# Roomba2.net
KiCad netlist of a schematic drawn in EAGLE
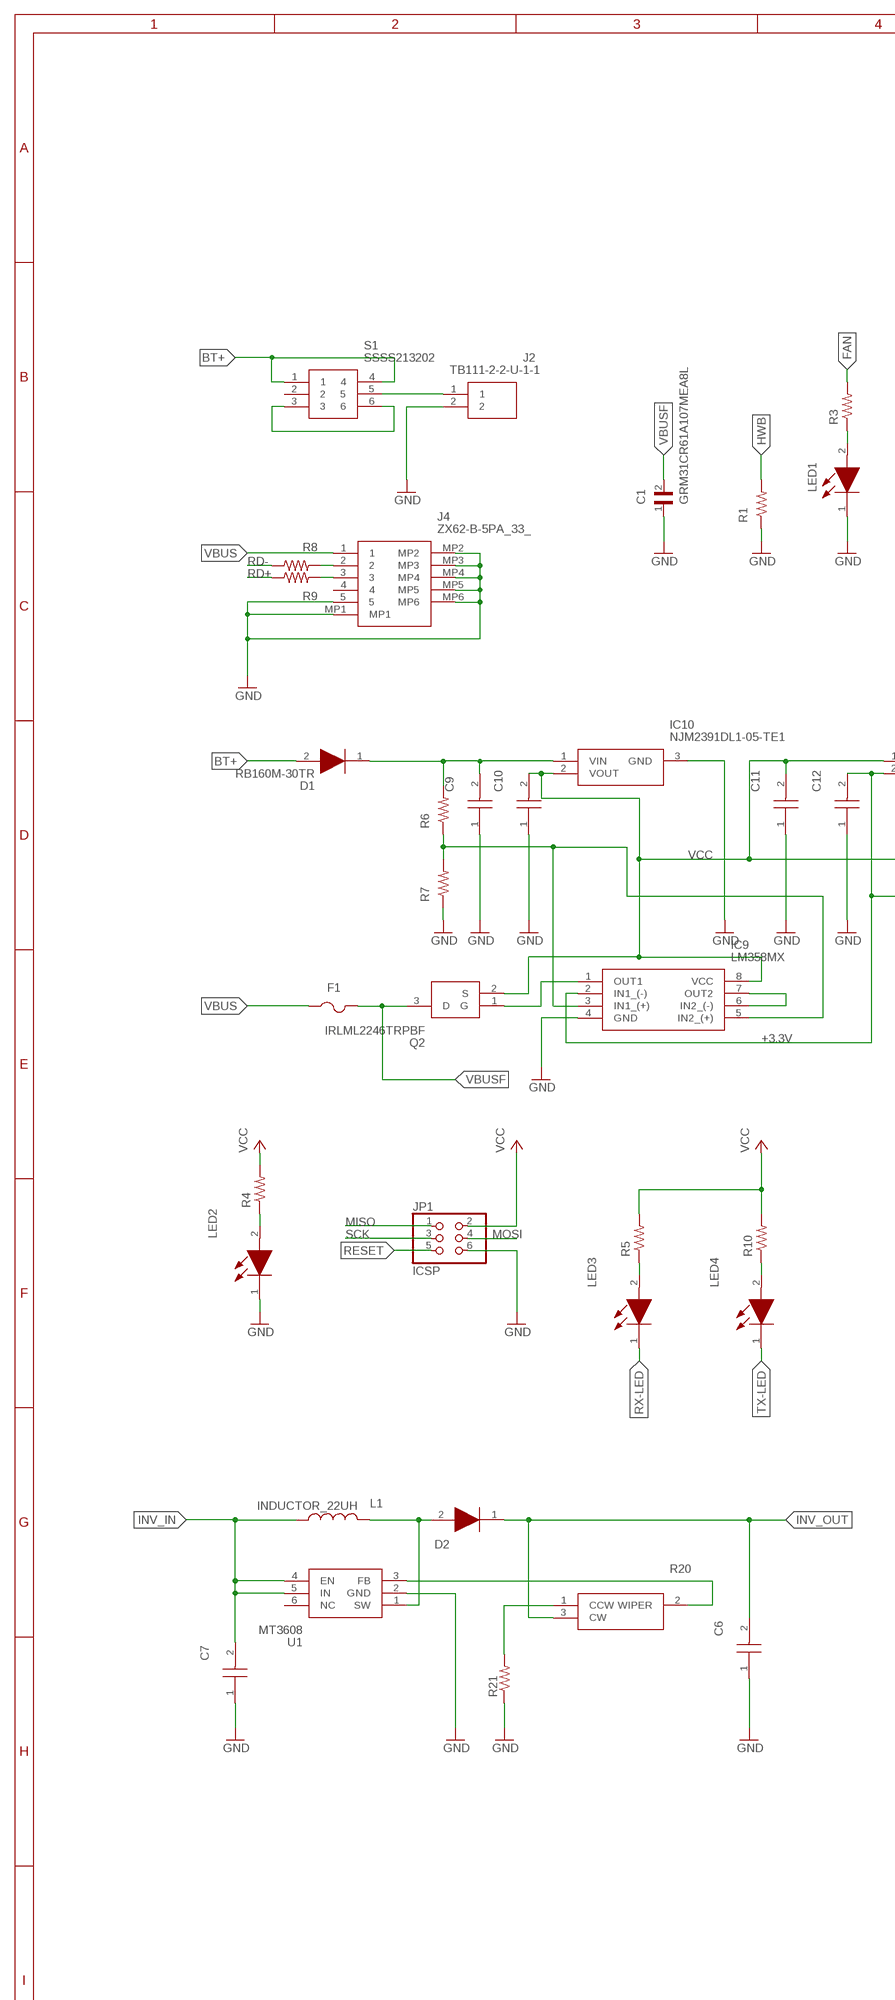
[diagram p0: schematic, sheet 1, part 1 of 2]
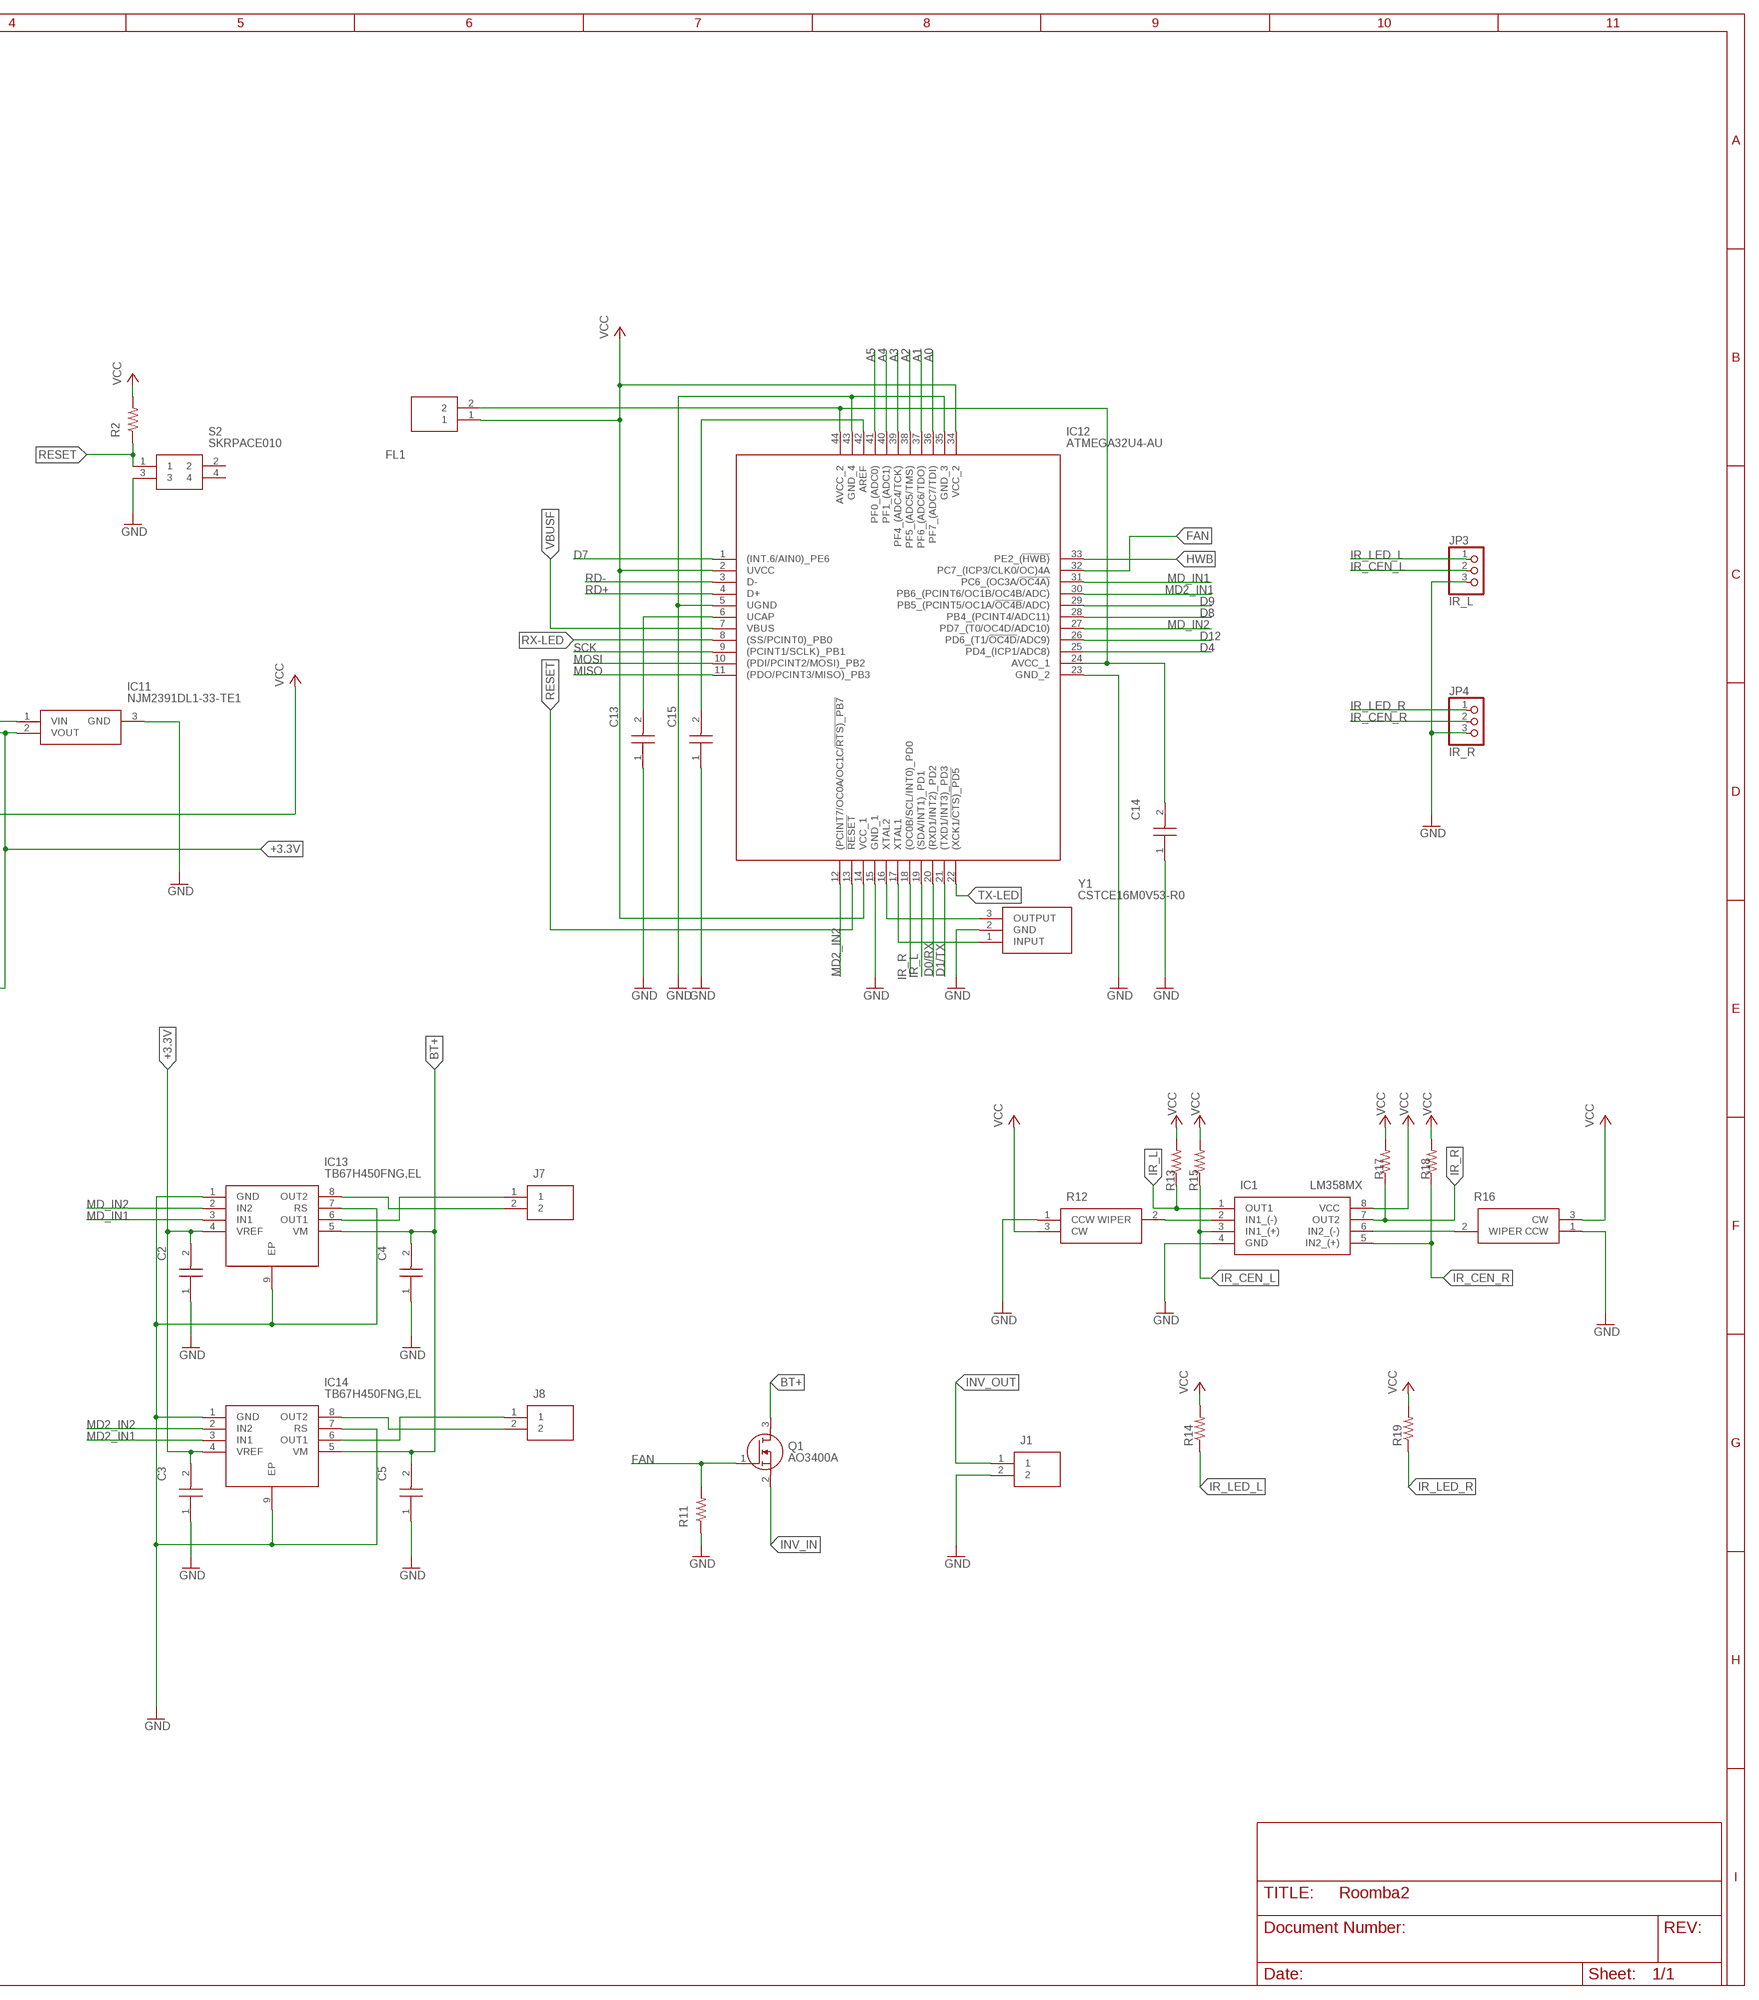
[diagram p1: schematic, sheet 1, part 2 of 2]

(export (version "E")
  (design (tool "Eeschema 10.0.6"))
  (components
    (comp (ref "C1")
      (value "GRM31CR61A107MEA8L")
      (footprint "eagle-import:CAPC3216X190N")
      (fields (field (name "MF") "Murata"))
      (libsource (lib "eagle-import") (part "GRM31CR61A107MEA8L"))
    )
    (comp (ref "C2")
      (value "GRM188F11H104ZA01B")
      (footprint "eagle-import:CAPC1608X90N")
      (libsource (lib "eagle-import") (part "GRM188F11H104ZA01B"))
    )
    (comp (ref "C3")
      (value "GRM188F11H104ZA01B")
      (footprint "eagle-import:CAPC1608X90N")
      (libsource (lib "eagle-import") (part "GRM188F11H104ZA01B"))
    )
    (comp (ref "C4")
      (value "GRM188F11H104ZA01B")
      (footprint "eagle-import:CAPC1608X90N")
      (libsource (lib "eagle-import") (part "GRM188F11H104ZA01B"))
    )
    (comp (ref "C5")
      (value "GRM188F11H104ZA01B")
      (footprint "eagle-import:CAPC1608X90N")
      (libsource (lib "eagle-import") (part "GRM188F11H104ZA01B"))
    )
    (comp (ref "C6")
      (value "GRM31CB31E226KE15L")
      (footprint "eagle-import:CAPC3216X180N")
      (libsource (lib "eagle-import") (part "GRM31CB31E226KE15L"))
    )
    (comp (ref "C7")
      (value "GRM31CB31E226KE15L")
      (footprint "eagle-import:CAPC3216X180N")
      (libsource (lib "eagle-import") (part "GRM31CB31E226KE15L"))
    )
    (comp (ref "C9")
      (value "GRM188F11H104ZA01B")
      (footprint "eagle-import:CAPC1608X90N")
      (libsource (lib "eagle-import") (part "GRM188F11H104ZA01B"))
    )
    (comp (ref "C10")
      (value "GRM31CB31A476KE15L")
      (footprint "eagle-import:CAPC3216X180N")
      (libsource (lib "eagle-import") (part "GRM31CB31A476KE15L"))
    )
    (comp (ref "C11")
      (value "GRM188F11H104ZA01B")
      (footprint "eagle-import:CAPC1608X90N")
      (libsource (lib "eagle-import") (part "GRM188F11H104ZA01B"))
    )
    (comp (ref "C12")
      (value "GRM31CB31A476KE15L")
      (footprint "eagle-import:CAPC3216X180N")
      (libsource (lib "eagle-import") (part "GRM31CB31A476KE15L"))
    )
    (comp (ref "C13")
      (value "GRM188R71E105KA12D")
      (footprint "eagle-import:CAPC1608X90N")
      (fields (field (name "MOUSER_PART_NUMBER") "81-GRM188R71E105KA2D"))
      (libsource (lib "eagle-import") (part "GRM188R71E105KA12D"))
    )
    (comp (ref "C14")
      (value "GRM188R71E105KA12D")
      (footprint "eagle-import:CAPC1608X90N")
      (fields (field (name "MOUSER_PART_NUMBER") "81-GRM188R71E105KA2D"))
      (libsource (lib "eagle-import") (part "GRM188R71E105KA12D"))
    )
    (comp (ref "C15")
      (value "GRM188F11H104ZA01B")
      (footprint "eagle-import:CAPC1608X90N")
      (libsource (lib "eagle-import") (part "GRM188F11H104ZA01B"))
    )
    (comp (ref "D1")
      (value "RB160M-30TR")
      (footprint "eagle-import:SODFL3516X90N")
      (fields (field (name "MOUSER_PART_NUMBER") "755-RB160M-30TR"))
      (libsource (lib "eagle-import") (part "RB160M-30TR"))
    )
    (comp (ref "D2")
      (value "SS2040FL")
      (footprint "eagle-import:SODFL3618X108N")
      (libsource (lib "eagle-import") (part "SS2040FL"))
    )
    (comp (ref "F1")
      (value "MF-MSMF010-2")
      (footprint "eagle-import:FUSC4632X110N")
      (fields (field (name "MOUSER_PART_NUMBER") "652-MF-MSMF010-2"))
      (libsource (lib "eagle-import") (part "MF-MSMF010-2"))
    )
    (comp (ref "FL1")
      (value "BLM18PG600SN1D")
      (footprint "eagle-import:BLM18AG102BH1D")
      (fields (field (name "MOUSER_PART_NUMBER") "81-BLM11P600S"))
      (libsource (lib "eagle-import") (part "BLM18PG600SN1D"))
    )
    (comp (ref "IC1")
      (value "LM358MX")
      (footprint "eagle-import:SOIC127P600X175-8N")
      (fields (field (name "MOUSER_PART_NUMBER") "512-LM358MX"))
      (libsource (lib "eagle-import") (part "LM358MX"))
    )
    (comp (ref "IC9")
      (value "LM358MX")
      (footprint "eagle-import:SOIC127P600X175-8N")
      (fields (field (name "MOUSER_PART_NUMBER") "512-LM358MX"))
      (libsource (lib "eagle-import") (part "LM358MX"))
    )
    (comp (ref "IC10")
      (value "NJM2391DL1-05-TE1")
      (footprint "eagle-import:TO-252-3-L1_1")
      (fields (field (name "MOUSER_PART_NUMBER") "513-NJM2391DL105-TE1"))
      (libsource (lib "eagle-import") (part "NJM2391DL1-05-TE1"))
    )
    (comp (ref "IC11")
      (value "NJM2391DL1-33-TE1")
      (footprint "eagle-import:TO-252-3-L1")
      (fields (field (name "MOUSER_PART_NUMBER") "513-NJM2391DL133-TE1"))
      (libsource (lib "eagle-import") (part "NJM2391DL1-33-TE1"))
    )
    (comp (ref "IC12")
      (value "ATMEGA32U4-AU")
      (footprint "eagle-import:QFP80P1200X1200X120-44N")
      (fields (field (name "MOUSER_PART_NUMBER") "556-ATMEGA32U4-AU"))
      (libsource (lib "eagle-import") (part "ATMEGA32U4-AU"))
    )
    (comp (ref "IC13")
      (value "TB67H450FNG,EL")
      (footprint "eagle-import:SOIC127P600X175-9N")
      (fields (field (name "MOUSER_PART_NUMBER") "757-TB67H450FNGEL"))
      (libsource (lib "eagle-import") (part "TB67H450FNG,EL"))
    )
    (comp (ref "IC14")
      (value "TB67H450FNG,EL")
      (footprint "eagle-import:SOIC127P600X175-9N")
      (fields (field (name "MOUSER_PART_NUMBER") "757-TB67H450FNGEL"))
      (libsource (lib "eagle-import") (part "TB67H450FNG,EL"))
    )
    (comp (ref "J1")
      (value "TB111-2-2-U-1-1")
      (footprint "eagle-import:TB11122U11")
      (libsource (lib "eagle-import") (part "TB111-2-2-U-1-1"))
    )
    (comp (ref "J2")
      (value "TB111-2-2-U-1-1")
      (footprint "eagle-import:TB11122U11")
      (libsource (lib "eagle-import") (part "TB111-2-2-U-1-1"))
    )
    (comp (ref "J4")
      (value "ZX62-B-5PA_33_")
      (footprint "eagle-import:ZX62B5PA33")
      (fields
        (field (name "MANUFACTURER_PART_NUMBER") "ZX62-B-5PA(33)")
        (field (name "MOUSER_PART_NUMBER") "798-ZX62-B-5PA33")
      )
      (libsource (lib "eagle-import") (part "ZX62-B-5PA_33_"))
    )
    (comp (ref "J7")
      (value "TB111-2-2-U-1-1")
      (footprint "eagle-import:TB11122U11")
      (libsource (lib "eagle-import") (part "TB111-2-2-U-1-1"))
    )
    (comp (ref "J8")
      (value "TB111-2-2-U-1-1")
      (footprint "eagle-import:TB11122U11")
      (libsource (lib "eagle-import") (part "TB111-2-2-U-1-1"))
    )
    (comp (ref "JP1")
      (value "ICSP")
      (footprint "eagle-import:2X03")
      (libsource (lib "eagle-import") (part "PINHD-2X3"))
    )
    (comp (ref "JP3")
      (value "IR_L")
      (footprint "eagle-import:1X03")
      (libsource (lib "eagle-import") (part "PINHD-1X3"))
    )
    (comp (ref "JP4")
      (value "IR_R")
      (footprint "eagle-import:1X03")
      (libsource (lib "eagle-import") (part "PINHD-1X3"))
    )
    (comp (ref "L1")
      (value "INDUCTOR_22UH")
      (footprint "eagle-import:INDUCTOR_22UH")
      (libsource (lib "eagle-import") (part "INDUCTOR_22UH"))
    )
    (comp (ref "LED1")
      (value "SML-E12Y8WT86")
      (footprint "eagle-import:SMLE12Y8WT86")
      (fields (field (name "MOUSER_PART_NUMBER") "755-SML-E12Y8WT86"))
      (libsource (lib "eagle-import") (part "SML-E12Y8WT86"))
    )
    (comp (ref "LED2")
      (value "SML-E12P8WT86")
      (footprint "eagle-import:LEDC1608X36N")
      (fields (field (name "MOUSER_PART_NUMBER") "755-SML-E12P8WT86"))
      (libsource (lib "eagle-import") (part "SML-E12P8WT86"))
    )
    (comp (ref "LED3")
      (value "SML-E12Y8WT86")
      (footprint "eagle-import:SMLE12Y8WT86")
      (fields (field (name "MOUSER_PART_NUMBER") "755-SML-E12Y8WT86"))
      (libsource (lib "eagle-import") (part "SML-E12Y8WT86"))
    )
    (comp (ref "LED4")
      (value "SML-E12Y8WT86")
      (footprint "eagle-import:SMLE12Y8WT86")
      (fields (field (name "MOUSER_PART_NUMBER") "755-SML-E12Y8WT86"))
      (libsource (lib "eagle-import") (part "SML-E12Y8WT86"))
    )
    (comp (ref "Q1")
      (value "AO3400A")
      (footprint "eagle-import:SOT95P280X125-3N")
      (libsource (lib "eagle-import") (part "AO3400A"))
    )
    (comp (ref "Q2")
      (value "IRLML2246TRPBF")
      (footprint "eagle-import:SOT95P237X112-3N")
      (fields (field (name "MOUSER_PART_NUMBER") "942-IRLML2246TRPBF"))
      (libsource (lib "eagle-import") (part "IRLML2246TRPBF"))
    )
    (comp (ref "R1")
      (value "CRCW120610K0FKEA")
      (footprint "eagle-import:RESC3216X60N")
      (fields (field (name "MOUSER_PART_NUMBER") "71-CRCW1206-10K-E3"))
      (libsource (lib "eagle-import") (part "CRCW120610K0FKEA"))
    )
    (comp (ref "R2")
      (value "CRCW120610K0FKEA")
      (footprint "eagle-import:RESC3216X60N")
      (fields (field (name "MOUSER_PART_NUMBER") "71-CRCW1206-10K-E3"))
      (libsource (lib "eagle-import") (part "CRCW120610K0FKEA"))
    )
    (comp (ref "R3")
      (value "CRCW12061K00FKEA")
      (footprint "eagle-import:RESC3216X60N")
      (fields (field (name "MOUSER_PART_NUMBER") "71-CRCW1206-1.0K-E3"))
      (libsource (lib "eagle-import") (part "CRCW12061K00FKEA"))
    )
    (comp (ref "R4")
      (value "CRCW12061K00FKEA")
      (footprint "eagle-import:RESC3216X60N")
      (fields (field (name "MOUSER_PART_NUMBER") "71-CRCW1206-1.0K-E3"))
      (libsource (lib "eagle-import") (part "CRCW12061K00FKEA"))
    )
    (comp (ref "R5")
      (value "CRCW12061K00FKEA")
      (footprint "eagle-import:RESC3216X60N")
      (fields (field (name "MOUSER_PART_NUMBER") "71-CRCW1206-1.0K-E3"))
      (libsource (lib "eagle-import") (part "CRCW12061K00FKEA"))
    )
    (comp (ref "R6")
      (value "CRCW120610K0FKEA")
      (footprint "eagle-import:RESC3216X60N")
      (fields (field (name "MOUSER_PART_NUMBER") "71-CRCW1206-10K-E3"))
      (libsource (lib "eagle-import") (part "CRCW120610K0FKEA"))
    )
    (comp (ref "R7")
      (value "CRCW120610K0FKEA")
      (footprint "eagle-import:RESC3216X60N")
      (fields (field (name "MOUSER_PART_NUMBER") "71-CRCW1206-10K-E3"))
      (libsource (lib "eagle-import") (part "CRCW120610K0FKEA"))
    )
    (comp (ref "R8")
      (value "CRCW120622R0FKEA")
      (footprint "eagle-import:RESC3216X60N")
      (fields (field (name "MOUSER_PART_NUMBER") "71-CRCW1206-22-E3"))
      (libsource (lib "eagle-import") (part "CRCW120622R0FKEA"))
    )
    (comp (ref "R9")
      (value "CRCW120622R0FKEA")
      (footprint "eagle-import:RESC3216X60N")
      (fields (field (name "MOUSER_PART_NUMBER") "71-CRCW1206-22-E3"))
      (libsource (lib "eagle-import") (part "CRCW120622R0FKEA"))
    )
    (comp (ref "R10")
      (value "CRCW12061K00FKEA")
      (footprint "eagle-import:RESC3216X60N")
      (fields (field (name "MOUSER_PART_NUMBER") "71-CRCW1206-1.0K-E3"))
      (libsource (lib "eagle-import") (part "CRCW12061K00FKEA"))
    )
    (comp (ref "R11")
      (value "CRCW120610K0FKEA")
      (footprint "eagle-import:RESC3216X60N")
      (fields (field (name "MOUSER_PART_NUMBER") "71-CRCW1206-10K-E3"))
      (libsource (lib "eagle-import") (part "CRCW120610K0FKEA"))
    )
    (comp (ref "R12")
      (value "3362P-1-103")
      (footprint "eagle-import:3362P_1")
      (fields (field (name "MOUSER_PART_NUMBER") "652-3362P-1-103"))
      (libsource (lib "eagle-import") (part "3362P-1-103"))
    )
    (comp (ref "R13")
      (value "CRCW120610K0FKEA")
      (footprint "eagle-import:RESC3216X60N")
      (fields (field (name "MOUSER_PART_NUMBER") "71-CRCW1206-10K-E3"))
      (libsource (lib "eagle-import") (part "CRCW120610K0FKEA"))
    )
    (comp (ref "R14")
      (value "CRCW1206100RFKEB")
      (footprint "eagle-import:RESC3216X60N")
      (fields (field (name "MOUSER_PART_NUMBER") "71-CRCW1206100RFKEB"))
      (libsource (lib "eagle-import") (part "CRCW1206100RFKEB"))
    )
    (comp (ref "R15")
      (value "CRCW120610K0FKEA")
      (footprint "eagle-import:RESC3216X60N")
      (fields (field (name "MOUSER_PART_NUMBER") "71-CRCW1206-10K-E3"))
      (libsource (lib "eagle-import") (part "CRCW120610K0FKEA"))
    )
    (comp (ref "R16")
      (value "3362P-1-103")
      (footprint "eagle-import:3362P_1")
      (fields (field (name "MOUSER_PART_NUMBER") "652-3362P-1-103"))
      (libsource (lib "eagle-import") (part "3362P-1-103"))
    )
    (comp (ref "R17")
      (value "CRCW120610K0FKEA")
      (footprint "eagle-import:RESC3216X60N")
      (fields (field (name "MOUSER_PART_NUMBER") "71-CRCW1206-10K-E3"))
      (libsource (lib "eagle-import") (part "CRCW120610K0FKEA"))
    )
    (comp (ref "R18")
      (value "CRCW120610K0FKEA")
      (footprint "eagle-import:RESC3216X60N")
      (fields (field (name "MOUSER_PART_NUMBER") "71-CRCW1206-10K-E3"))
      (libsource (lib "eagle-import") (part "CRCW120610K0FKEA"))
    )
    (comp (ref "R19")
      (value "CRCW1206100RFKEB")
      (footprint "eagle-import:RESC3216X60N")
      (fields (field (name "MOUSER_PART_NUMBER") "71-CRCW1206100RFKEB"))
      (libsource (lib "eagle-import") (part "CRCW1206100RFKEB"))
    )
    (comp (ref "R20")
      (value "3362P-1-104LF")
      (footprint "eagle-import:3362P_1")
      (fields (field (name "MOUSER_PART_NUMBER") "652-3362P-1-104LF"))
      (libsource (lib "eagle-import") (part "3362P-1-104LF"))
    )
    (comp (ref "R21")
      (value "CRCW12062K20FKEA")
      (footprint "eagle-import:RESC3216X60N")
      (fields (field (name "MOUSER_PART_NUMBER") "71-CRCW1206-2.2K-E3"))
      (libsource (lib "eagle-import") (part "CRCW12062K20FKEA"))
    )
    (comp (ref "S1")
      (value "SSSS213202")
      (footprint "eagle-import:SSSS213202")
      (fields (field (name "MOUSER_PART_NUMBER") "688-SSSS213202"))
      (libsource (lib "eagle-import") (part "SSSS213202"))
    )
    (comp (ref "S2")
      (value "SKRPACE010")
      (footprint "eagle-import:SMT(4.2X3.2)")
      (fields (field (name "MOUSER_PART_NUMBER") "688-SKRPACE010"))
      (libsource (lib "eagle-import") (part "SKRPACE010"))
    )
    (comp (ref "U1")
      (value "MT3608")
      (footprint "eagle-import:SOT95P280X145-6N")
      (libsource (lib "eagle-import") (part "MT3608"))
    )
    (comp (ref "Y1")
      (value "CSTCE16M0V53-R0")
      (footprint "eagle-import:CSTCE16M0V53R0")
      (fields (field (name "MOUSER_PART_NUMBER") "81-CSTCE16M0V53-R0"))
      (libsource (lib "eagle-import") (part "CSTCE16M0V53-R0"))
    )
  )
  (nets
    (net (code "1") (name "+3.3V") (class "Default")
      (node (ref "C12") (pin "2") (pinfunction "2_2") (pintype "bidirectional"))
      (node (ref "C2") (pin "2") (pinfunction "2_2") (pintype "bidirectional"))
      (node (ref "C3") (pin "2") (pinfunction "2_2") (pintype "bidirectional"))
      (node (ref "IC11") (pin "2") (pinfunction "VOUT_2") (pintype "bidirectional"))
      (node (ref "IC13") (pin "4") (pinfunction "VREF_4") (pintype "bidirectional"))
      (node (ref "IC14") (pin "4") (pinfunction "VREF_4") (pintype "bidirectional"))
      (node (ref "IC9") (pin "2") (pinfunction "IN1_(-)_2") (pintype "bidirectional"))
    )
    (net (code "2") (name "/A0") (class "Default")
      (node (ref "IC12") (pin "36") (pinfunction "PF7_(ADC7/TDI)_36") (pintype "bidirectional"))
    )
    (net (code "3") (name "/A1") (class "Default")
      (node (ref "IC12") (pin "37") (pinfunction "PF6_(ADC6/TDO)_37") (pintype "bidirectional"))
    )
    (net (code "4") (name "/A2") (class "Default")
      (node (ref "IC12") (pin "38") (pinfunction "PF5_(ADC5/TMS)_38") (pintype "bidirectional"))
    )
    (net (code "5") (name "/A3") (class "Default")
      (node (ref "IC12") (pin "39") (pinfunction "PF4_(ADC4/TCK)_39") (pintype "bidirectional"))
    )
    (net (code "6") (name "/A4") (class "Default")
      (node (ref "IC12") (pin "40") (pinfunction "PF1_(ADC1)_40") (pintype "bidirectional"))
    )
    (net (code "7") (name "/A5") (class "Default")
      (node (ref "IC12") (pin "41") (pinfunction "PF0_(ADC0)_41") (pintype "bidirectional"))
    )
    (net (code "8") (name "/D0{slash}RX") (class "Default")
      (node (ref "IC12") (pin "20") (pinfunction "(RXD1/INT2)_PD2_20") (pintype "bidirectional"))
    )
    (net (code "9") (name "/D1{slash}TX") (class "Default")
      (node (ref "IC12") (pin "21") (pinfunction "(TXD1/INT3)_PD3_21") (pintype "bidirectional"))
    )
    (net (code "10") (name "/D4") (class "Default")
      (node (ref "IC12") (pin "25") (pinfunction "PD4_(ICP1/ADC8)_25") (pintype "bidirectional"))
    )
    (net (code "11") (name "/D7") (class "Default")
      (node (ref "IC12") (pin "1") (pinfunction "(INT.6/AIN0)_PE6_1") (pintype "bidirectional"))
    )
    (net (code "12") (name "/D8") (class "Default")
      (node (ref "IC12") (pin "28") (pinfunction "PB4_(PCINT4/ADC11)_28") (pintype "bidirectional"))
    )
    (net (code "13") (name "/D9") (class "Default")
      (node (ref "IC12") (pin "29") (pinfunction "PB5_(PCINT5/OC1A/~{OC4B}/ADC)_29") (pintype "bidirectional"))
    )
    (net (code "14") (name "/D12") (class "Default")
      (node (ref "IC12") (pin "26") (pinfunction "PD6_(T1/~{OC4D}/ADC9)_26") (pintype "bidirectional"))
    )
    (net (code "15") (name "/MD2_IN1") (class "Default")
      (node (ref "IC12") (pin "30") (pinfunction "PB6_(PCINT6/OC1B/OC4B/ADC)_30") (pintype "bidirectional"))
      (node (ref "IC14") (pin "3") (pinfunction "IN1_3") (pintype "bidirectional"))
    )
    (net (code "16") (name "/MD2_IN2") (class "Default")
      (node (ref "IC12") (pin "12") (pinfunction "(PCINT7/OC0A/OC1C/~{RTS})_PB7_12") (pintype "bidirectional"))
      (node (ref "IC14") (pin "2") (pinfunction "IN2_2") (pintype "bidirectional"))
    )
    (net (code "17") (name "/MD_IN1") (class "Default")
      (node (ref "IC12") (pin "31") (pinfunction "PC6_(OC3A/~{OC4A})_31") (pintype "bidirectional"))
      (node (ref "IC13") (pin "3") (pinfunction "IN1_3") (pintype "bidirectional"))
    )
    (net (code "18") (name "/MD_IN2") (class "Default")
      (node (ref "IC12") (pin "27") (pinfunction "PD7_(T0/OC4D/ADC10)_27") (pintype "bidirectional"))
      (node (ref "IC13") (pin "2") (pinfunction "IN2_2") (pintype "bidirectional"))
    )
    (net (code "19") (name "/MISO") (class "Default")
      (node (ref "IC12") (pin "11") (pinfunction "(PDO/PCINT3/MISO)_PB3_11") (pintype "bidirectional"))
      (node (ref "JP1") (pin "1") (pinfunction "1_1") (pintype "passive"))
    )
    (net (code "20") (name "/MOSI") (class "Default")
      (node (ref "IC12") (pin "10") (pinfunction "(PDI/PCINT2/MOSI)_PB2_10") (pintype "bidirectional"))
      (node (ref "JP1") (pin "4") (pinfunction "4_4") (pintype "passive"))
    )
    (net (code "21") (name "/RD+") (class "Default")
      (node (ref "IC12") (pin "4") (pinfunction "D+_4") (pintype "bidirectional"))
      (node (ref "R9") (pin "1") (pinfunction "1_1") (pintype "passive"))
    )
    (net (code "22") (name "/RD-") (class "Default")
      (node (ref "IC12") (pin "3") (pinfunction "D-_3") (pintype "bidirectional"))
      (node (ref "R8") (pin "1") (pinfunction "1_1") (pintype "passive"))
    )
    (net (code "23") (name "/SCK") (class "Default")
      (node (ref "IC12") (pin "9") (pinfunction "(PCINT1/SCLK)_PB1_9") (pintype "bidirectional"))
      (node (ref "JP1") (pin "3") (pinfunction "3_3") (pintype "passive"))
    )
    (net (code "24") (name "BT+") (class "Default")
      (node (ref "C4") (pin "2") (pinfunction "2_2") (pintype "bidirectional"))
      (node (ref "C5") (pin "2") (pinfunction "2_2") (pintype "bidirectional"))
      (node (ref "D1") (pin "2") (pinfunction "A_2") (pintype "bidirectional"))
      (node (ref "IC13") (pin "5") (pinfunction "VM_5") (pintype "bidirectional"))
      (node (ref "IC14") (pin "5") (pinfunction "VM_5") (pintype "bidirectional"))
      (node (ref "Q1") (pin "3") (pinfunction "D_3") (pintype "bidirectional"))
      (node (ref "S1") (pin "1") (pinfunction "1_1") (pintype "bidirectional"))
      (node (ref "S1") (pin "4") (pinfunction "4_4") (pintype "bidirectional"))
    )
    (net (code "25") (name "FAN") (class "Default")
      (node (ref "IC12") (pin "32") (pinfunction "PC7_(ICP3/CLK0/OC)4A_32") (pintype "bidirectional"))
      (node (ref "Q1") (pin "1") (pinfunction "G_1") (pintype "bidirectional"))
      (node (ref "R11") (pin "2") (pinfunction "2_2") (pintype "passive"))
      (node (ref "R3") (pin "2") (pinfunction "2_2") (pintype "passive"))
    )
    (net (code "26") (name "GND") (class "Default")
      (node (ref "C1") (pin "1") (pinfunction "1_1") (pintype "passive"))
      (node (ref "C10") (pin "1") (pinfunction "1_1") (pintype "bidirectional"))
      (node (ref "C11") (pin "1") (pinfunction "1_1") (pintype "bidirectional"))
      (node (ref "C12") (pin "1") (pinfunction "1_1") (pintype "bidirectional"))
      (node (ref "C13") (pin "1") (pinfunction "1_1") (pintype "bidirectional"))
      (node (ref "C14") (pin "1") (pinfunction "1_1") (pintype "bidirectional"))
      (node (ref "C15") (pin "1") (pinfunction "1_1") (pintype "bidirectional"))
      (node (ref "C2") (pin "1") (pinfunction "1_1") (pintype "bidirectional"))
      (node (ref "C3") (pin "1") (pinfunction "1_1") (pintype "bidirectional"))
      (node (ref "C4") (pin "1") (pinfunction "1_1") (pintype "bidirectional"))
      (node (ref "C5") (pin "1") (pinfunction "1_1") (pintype "bidirectional"))
      (node (ref "C6") (pin "1") (pinfunction "1_1") (pintype "bidirectional"))
      (node (ref "C7") (pin "1") (pinfunction "1_1") (pintype "bidirectional"))
      (node (ref "C9") (pin "1") (pinfunction "1_1") (pintype "bidirectional"))
      (node (ref "IC1") (pin "4") (pinfunction "GND_4") (pintype "bidirectional"))
      (node (ref "IC10") (pin "3") (pinfunction "GND_3") (pintype "bidirectional"))
      (node (ref "IC11") (pin "3") (pinfunction "GND_3") (pintype "bidirectional"))
      (node (ref "IC12") (pin "15") (pinfunction "GND_1_15") (pintype "bidirectional"))
      (node (ref "IC12") (pin "23") (pinfunction "GND_2_23") (pintype "bidirectional"))
      (node (ref "IC12") (pin "35") (pinfunction "GND_3_35") (pintype "bidirectional"))
      (node (ref "IC12") (pin "43") (pinfunction "GND_4_43") (pintype "bidirectional"))
      (node (ref "IC12") (pin "5") (pinfunction "UGND_5") (pintype "bidirectional"))
      (node (ref "IC13") (pin "1") (pinfunction "GND_1") (pintype "bidirectional"))
      (node (ref "IC13") (pin "7") (pinfunction "RS_7") (pintype "bidirectional"))
      (node (ref "IC13") (pin "9") (pinfunction "EP_9") (pintype "bidirectional"))
      (node (ref "IC14") (pin "1") (pinfunction "GND_1") (pintype "bidirectional"))
      (node (ref "IC14") (pin "7") (pinfunction "RS_7") (pintype "bidirectional"))
      (node (ref "IC14") (pin "9") (pinfunction "EP_9") (pintype "bidirectional"))
      (node (ref "IC9") (pin "4") (pinfunction "GND_4") (pintype "bidirectional"))
      (node (ref "J1") (pin "2") (pinfunction "2_2") (pintype "bidirectional"))
      (node (ref "J2") (pin "2") (pinfunction "2_2") (pintype "bidirectional"))
      (node (ref "J4") (pin "5") (pinfunction "5_5") (pintype "bidirectional"))
      (node (ref "J4") (pin "MP1") (pinfunction "MP1_MP1") (pintype "bidirectional"))
      (node (ref "J4") (pin "MP2") (pinfunction "MP2_MP2") (pintype "bidirectional"))
      (node (ref "J4") (pin "MP3") (pinfunction "MP3_MP3") (pintype "bidirectional"))
      (node (ref "J4") (pin "MP4") (pinfunction "MP4_MP4") (pintype "bidirectional"))
      (node (ref "J4") (pin "MP5") (pinfunction "MP5_MP5") (pintype "bidirectional"))
      (node (ref "J4") (pin "MP6") (pinfunction "MP6_MP6") (pintype "bidirectional"))
      (node (ref "JP1") (pin "6") (pinfunction "6_6") (pintype "passive"))
      (node (ref "JP3") (pin "3") (pinfunction "3_3") (pintype "passive"))
      (node (ref "JP4") (pin "3") (pinfunction "3_3") (pintype "passive"))
      (node (ref "LED1") (pin "1") (pinfunction "K_1") (pintype "bidirectional"))
      (node (ref "LED2") (pin "1") (pinfunction "K_1") (pintype "bidirectional"))
      (node (ref "R1") (pin "1") (pinfunction "1_1") (pintype "passive"))
      (node (ref "R11") (pin "1") (pinfunction "1_1") (pintype "passive"))
      (node (ref "R12") (pin "1") (pinfunction "CCW_1") (pintype "bidirectional"))
      (node (ref "R16") (pin "1") (pinfunction "CCW_1") (pintype "bidirectional"))
      (node (ref "R21") (pin "1") (pinfunction "1_1") (pintype "passive"))
      (node (ref "R7") (pin "1") (pinfunction "1_1") (pintype "passive"))
      (node (ref "S2") (pin "3") (pinfunction "3_3") (pintype "bidirectional"))
      (node (ref "U1") (pin "2") (pinfunction "GND_2") (pintype "bidirectional"))
      (node (ref "Y1") (pin "2") (pinfunction "GND_2") (pintype "bidirectional"))
    )
    (net (code "27") (name "HWB") (class "Default")
      (node (ref "IC12") (pin "33") (pinfunction "PE2_(~{HWB})_33") (pintype "bidirectional"))
      (node (ref "R1") (pin "2") (pinfunction "2_2") (pintype "passive"))
    )
    (net (code "28") (name "INV_IN") (class "Default")
      (node (ref "C7") (pin "2") (pinfunction "2_2") (pintype "bidirectional"))
      (node (ref "L1") (pin "P$1") (pinfunction "1_P$1") (pintype "passive"))
      (node (ref "Q1") (pin "2") (pinfunction "S_2") (pintype "bidirectional"))
      (node (ref "U1") (pin "4") (pinfunction "EN_4") (pintype "bidirectional"))
      (node (ref "U1") (pin "5") (pinfunction "IN_5") (pintype "bidirectional"))
    )
    (net (code "29") (name "INV_OUT") (class "Default")
      (node (ref "C6") (pin "2") (pinfunction "2_2") (pintype "bidirectional"))
      (node (ref "D2") (pin "1") (pinfunction "K_1") (pintype "bidirectional"))
      (node (ref "J1") (pin "1") (pinfunction "1_1") (pintype "bidirectional"))
      (node (ref "R20") (pin "3") (pinfunction "CW_3") (pintype "bidirectional"))
    )
    (net (code "30") (name "IR_CEN_L") (class "Default")
      (node (ref "IC1") (pin "3") (pinfunction "IN1_(+)_3") (pintype "bidirectional"))
      (node (ref "JP3") (pin "2") (pinfunction "2_2") (pintype "passive"))
      (node (ref "R15") (pin "1") (pinfunction "1_1") (pintype "passive"))
    )
    (net (code "31") (name "IR_CEN_R") (class "Default")
      (node (ref "IC1") (pin "5") (pinfunction "IN2_(+)_5") (pintype "bidirectional"))
      (node (ref "JP4") (pin "2") (pinfunction "2_2") (pintype "passive"))
      (node (ref "R18") (pin "1") (pinfunction "1_1") (pintype "passive"))
    )
    (net (code "32") (name "IR_L") (class "Default")
      (node (ref "IC1") (pin "1") (pinfunction "OUT1_1") (pintype "bidirectional"))
      (node (ref "IC12") (pin "19") (pinfunction "(SDA/INT1)_PD1_19") (pintype "bidirectional"))
      (node (ref "R13") (pin "1") (pinfunction "1_1") (pintype "passive"))
    )
    (net (code "33") (name "IR_LED_L") (class "Default")
      (node (ref "JP3") (pin "1") (pinfunction "1_1") (pintype "passive"))
      (node (ref "R14") (pin "1") (pinfunction "1_1") (pintype "passive"))
    )
    (net (code "34") (name "IR_LED_R") (class "Default")
      (node (ref "JP4") (pin "1") (pinfunction "1_1") (pintype "passive"))
      (node (ref "R19") (pin "1") (pinfunction "1_1") (pintype "passive"))
    )
    (net (code "35") (name "IR_R") (class "Default")
      (node (ref "IC1") (pin "7") (pinfunction "OUT2_7") (pintype "bidirectional"))
      (node (ref "IC12") (pin "18") (pinfunction "(OC0B/SCL/INT0)_PD0_18") (pintype "bidirectional"))
      (node (ref "R17") (pin "1") (pinfunction "1_1") (pintype "passive"))
    )
    (net (code "36") (name "Net-(D1-K)") (class "Default")
      (node (ref "C9") (pin "2") (pinfunction "2_2") (pintype "bidirectional"))
      (node (ref "D1") (pin "1") (pinfunction "K_1") (pintype "bidirectional"))
      (node (ref "IC10") (pin "1") (pinfunction "VIN_1") (pintype "bidirectional"))
      (node (ref "R6") (pin "2") (pinfunction "2_2") (pintype "passive"))
    )
    (net (code "37") (name "Net-(D2-A)") (class "Default")
      (node (ref "D2") (pin "2") (pinfunction "A_2") (pintype "bidirectional"))
      (node (ref "L1") (pin "P$2") (pinfunction "2_P$2") (pintype "passive"))
      (node (ref "U1") (pin "1") (pinfunction "SW_1") (pintype "bidirectional"))
    )
    (net (code "38") (name "Net-(IC1-IN1_(-))") (class "Default")
      (node (ref "IC1") (pin "2") (pinfunction "IN1_(-)_2") (pintype "bidirectional"))
      (node (ref "R12") (pin "2") (pinfunction "WIPER_2") (pintype "bidirectional"))
    )
    (net (code "39") (name "Net-(IC1-IN2_(-))") (class "Default")
      (node (ref "IC1") (pin "6") (pinfunction "IN2_(-)_6") (pintype "bidirectional"))
      (node (ref "R16") (pin "2") (pinfunction "WIPER_2") (pintype "bidirectional"))
    )
    (net (code "40") (name "Net-(IC9-IN1_(+))") (class "Default")
      (node (ref "IC9") (pin "3") (pinfunction "IN1_(+)_3") (pintype "bidirectional"))
      (node (ref "IC9") (pin "5") (pinfunction "IN2_(+)_5") (pintype "bidirectional"))
      (node (ref "R6") (pin "1") (pinfunction "1_1") (pintype "passive"))
      (node (ref "R7") (pin "2") (pinfunction "2_2") (pintype "passive"))
    )
    (net (code "41") (name "Net-(IC9-IN2_(-))") (class "Default")
      (node (ref "IC9") (pin "6") (pinfunction "IN2_(-)_6") (pintype "bidirectional"))
      (node (ref "IC9") (pin "7") (pinfunction "OUT2_7") (pintype "bidirectional"))
    )
    (net (code "42") (name "Net-(IC9-OUT1)") (class "Default")
      (node (ref "IC9") (pin "1") (pinfunction "OUT1_1") (pintype "bidirectional"))
      (node (ref "Q2") (pin "1") (pinfunction "G_1") (pintype "bidirectional"))
    )
    (net (code "43") (name "Net-(IC12-AREF)") (class "Default")
      (node (ref "C15") (pin "2") (pinfunction "2_2") (pintype "bidirectional"))
      (node (ref "IC12") (pin "42") (pinfunction "AREF_42") (pintype "bidirectional"))
    )
    (net (code "44") (name "Net-(IC12-AVCC_1)") (class "Default")
      (node (ref "C14") (pin "2") (pinfunction "2_2") (pintype "bidirectional"))
      (node (ref "FL1") (pin "2") (pinfunction "2_2") (pintype "bidirectional"))
      (node (ref "IC12") (pin "24") (pinfunction "AVCC_1_24") (pintype "bidirectional"))
      (node (ref "IC12") (pin "44") (pinfunction "AVCC_2_44") (pintype "bidirectional"))
    )
    (net (code "45") (name "Net-(IC12-UCAP)") (class "Default")
      (node (ref "C13") (pin "2") (pinfunction "2_2") (pintype "bidirectional"))
      (node (ref "IC12") (pin "6") (pinfunction "UCAP_6") (pintype "bidirectional"))
    )
    (net (code "46") (name "Net-(IC12-XTAL1)") (class "Default")
      (node (ref "IC12") (pin "17") (pinfunction "XTAL1_17") (pintype "bidirectional"))
      (node (ref "Y1") (pin "1") (pinfunction "INPUT_1") (pintype "bidirectional"))
    )
    (net (code "47") (name "Net-(IC12-XTAL2)") (class "Default")
      (node (ref "IC12") (pin "16") (pinfunction "XTAL2_16") (pintype "bidirectional"))
      (node (ref "Y1") (pin "3") (pinfunction "OUTPUT_3") (pintype "bidirectional"))
    )
    (net (code "48") (name "Net-(IC13-OUT1)") (class "Default")
      (node (ref "IC13") (pin "6") (pinfunction "OUT1_6") (pintype "bidirectional"))
      (node (ref "J7") (pin "1") (pinfunction "1_1") (pintype "bidirectional"))
    )
    (net (code "49") (name "Net-(IC13-OUT2)") (class "Default")
      (node (ref "IC13") (pin "8") (pinfunction "OUT2_8") (pintype "bidirectional"))
      (node (ref "J7") (pin "2") (pinfunction "2_2") (pintype "bidirectional"))
    )
    (net (code "50") (name "Net-(IC14-OUT1)") (class "Default")
      (node (ref "IC14") (pin "6") (pinfunction "OUT1_6") (pintype "bidirectional"))
      (node (ref "J8") (pin "1") (pinfunction "1_1") (pintype "bidirectional"))
    )
    (net (code "51") (name "Net-(IC14-OUT2)") (class "Default")
      (node (ref "IC14") (pin "8") (pinfunction "OUT2_8") (pintype "bidirectional"))
      (node (ref "J8") (pin "2") (pinfunction "2_2") (pintype "bidirectional"))
    )
    (net (code "52") (name "Net-(J2-Pad1)") (class "Default")
      (node (ref "J2") (pin "1") (pinfunction "1_1") (pintype "bidirectional"))
      (node (ref "S1") (pin "5") (pinfunction "5_5") (pintype "bidirectional"))
    )
    (net (code "53") (name "Net-(J4-Pad2)") (class "Default")
      (node (ref "J4") (pin "2") (pinfunction "2_2") (pintype "bidirectional"))
      (node (ref "R8") (pin "2") (pinfunction "2_2") (pintype "passive"))
    )
    (net (code "54") (name "Net-(J4-Pad3)") (class "Default")
      (node (ref "J4") (pin "3") (pinfunction "3_3") (pintype "bidirectional"))
      (node (ref "R9") (pin "2") (pinfunction "2_2") (pintype "passive"))
    )
    (net (code "55") (name "Net-(LED1-A)") (class "Default")
      (node (ref "LED1") (pin "2") (pinfunction "A_2") (pintype "bidirectional"))
      (node (ref "R3") (pin "1") (pinfunction "1_1") (pintype "passive"))
    )
    (net (code "56") (name "Net-(LED2-A)") (class "Default")
      (node (ref "LED2") (pin "2") (pinfunction "A_2") (pintype "bidirectional"))
      (node (ref "R4") (pin "1") (pinfunction "1_1") (pintype "passive"))
    )
    (net (code "57") (name "Net-(LED3-A)") (class "Default")
      (node (ref "LED3") (pin "2") (pinfunction "A_2") (pintype "bidirectional"))
      (node (ref "R5") (pin "1") (pinfunction "1_1") (pintype "passive"))
    )
    (net (code "58") (name "Net-(LED4-A)") (class "Default")
      (node (ref "LED4") (pin "2") (pinfunction "A_2") (pintype "bidirectional"))
      (node (ref "R10") (pin "1") (pinfunction "1_1") (pintype "passive"))
    )
    (net (code "59") (name "Net-(R20-CCW)") (class "Default")
      (node (ref "R20") (pin "1") (pinfunction "CCW_1") (pintype "bidirectional"))
      (node (ref "R21") (pin "2") (pinfunction "2_2") (pintype "passive"))
    )
    (net (code "60") (name "Net-(R20-WIPER)") (class "Default")
      (node (ref "R20") (pin "2") (pinfunction "WIPER_2") (pintype "bidirectional"))
      (node (ref "U1") (pin "3") (pinfunction "FB_3") (pintype "bidirectional"))
    )
    (net (code "61") (name "Net-(S1-Pad3)") (class "Default")
      (node (ref "S1") (pin "3") (pinfunction "3_3") (pintype "bidirectional"))
      (node (ref "S1") (pin "6") (pinfunction "6_6") (pintype "bidirectional"))
    )
    (net (code "62") (name "RESET") (class "Default")
      (node (ref "IC12") (pin "13") (pinfunction "~{RESET}_13") (pintype "bidirectional"))
      (node (ref "JP1") (pin "5") (pinfunction "5_5") (pintype "passive"))
      (node (ref "R2") (pin "1") (pinfunction "1_1") (pintype "passive"))
      (node (ref "S2") (pin "1") (pinfunction "1_1") (pintype "bidirectional"))
    )
    (net (code "63") (name "RX-LED") (class "Default")
      (node (ref "IC12") (pin "8") (pinfunction "(SS/PCINT0)_PB0_8") (pintype "bidirectional"))
      (node (ref "LED3") (pin "1") (pinfunction "K_1") (pintype "bidirectional"))
    )
    (net (code "64") (name "TX-LED") (class "Default")
      (node (ref "IC12") (pin "22") (pinfunction "(XCK1/~{CTS})_PD5_22") (pintype "bidirectional"))
      (node (ref "LED4") (pin "1") (pinfunction "K_1") (pintype "bidirectional"))
    )
    (net (code "65") (name "VBUS") (class "Default")
      (node (ref "F1") (pin "1") (pinfunction "1_1") (pintype "passive"))
      (node (ref "J4") (pin "1") (pinfunction "1_1") (pintype "bidirectional"))
    )
    (net (code "66") (name "VBUSF") (class "Default")
      (node (ref "C1") (pin "2") (pinfunction "2_2") (pintype "passive"))
      (node (ref "F1") (pin "2") (pinfunction "2_2") (pintype "passive"))
      (node (ref "IC12") (pin "7") (pinfunction "VBUS_7") (pintype "bidirectional"))
      (node (ref "Q2") (pin "3") (pinfunction "D_3") (pintype "bidirectional"))
    )
    (net (code "67") (name "VCC") (class "Default")
      (node (ref "C10") (pin "2") (pinfunction "2_2") (pintype "bidirectional"))
      (node (ref "C11") (pin "2") (pinfunction "2_2") (pintype "bidirectional"))
      (node (ref "FL1") (pin "1") (pinfunction "1_1") (pintype "bidirectional"))
      (node (ref "IC1") (pin "8") (pinfunction "VCC_8") (pintype "bidirectional"))
      (node (ref "IC10") (pin "2") (pinfunction "VOUT_2") (pintype "bidirectional"))
      (node (ref "IC11") (pin "1") (pinfunction "VIN_1") (pintype "bidirectional"))
      (node (ref "IC12") (pin "14") (pinfunction "VCC_1_14") (pintype "bidirectional"))
      (node (ref "IC12") (pin "2") (pinfunction "UVCC_2") (pintype "bidirectional"))
      (node (ref "IC12") (pin "34") (pinfunction "VCC_2_34") (pintype "bidirectional"))
      (node (ref "IC9") (pin "8") (pinfunction "VCC_8") (pintype "bidirectional"))
      (node (ref "JP1") (pin "2") (pinfunction "2_2") (pintype "passive"))
      (node (ref "Q2") (pin "2") (pinfunction "S_2") (pintype "bidirectional"))
      (node (ref "R10") (pin "2") (pinfunction "2_2") (pintype "passive"))
      (node (ref "R12") (pin "3") (pinfunction "CW_3") (pintype "bidirectional"))
      (node (ref "R13") (pin "2") (pinfunction "2_2") (pintype "passive"))
      (node (ref "R14") (pin "2") (pinfunction "2_2") (pintype "passive"))
      (node (ref "R15") (pin "2") (pinfunction "2_2") (pintype "passive"))
      (node (ref "R16") (pin "3") (pinfunction "CW_3") (pintype "bidirectional"))
      (node (ref "R17") (pin "2") (pinfunction "2_2") (pintype "passive"))
      (node (ref "R18") (pin "2") (pinfunction "2_2") (pintype "passive"))
      (node (ref "R19") (pin "2") (pinfunction "2_2") (pintype "passive"))
      (node (ref "R2") (pin "2") (pinfunction "2_2") (pintype "passive"))
      (node (ref "R4") (pin "2") (pinfunction "2_2") (pintype "passive"))
      (node (ref "R5") (pin "2") (pinfunction "2_2") (pintype "passive"))
    )
    (net (code "68") (name "unconnected-(J4-Pad4)") (class "Default")
      (node (ref "J4") (pin "4") (pinfunction "4_4") (pintype "bidirectional"))
    )
    (net (code "69") (name "unconnected-(S1-Pad2)") (class "Default")
      (node (ref "S1") (pin "2") (pinfunction "2_2") (pintype "bidirectional"))
    )
    (net (code "70") (name "unconnected-(S2-Pad2)") (class "Default")
      (node (ref "S2") (pin "2") (pinfunction "2_2") (pintype "bidirectional"))
    )
    (net (code "71") (name "unconnected-(S2-Pad4)") (class "Default")
      (node (ref "S2") (pin "4") (pinfunction "4_4") (pintype "bidirectional"))
    )
    (net (code "72") (name "unconnected-(U1-NC-Pad6)") (class "Default")
      (node (ref "U1") (pin "6") (pinfunction "NC_6") (pintype "no_connect"))
    )
  )
)
